# HMC5983_Breakout.net
KiCad netlist of a schematic drawn in EAGLE
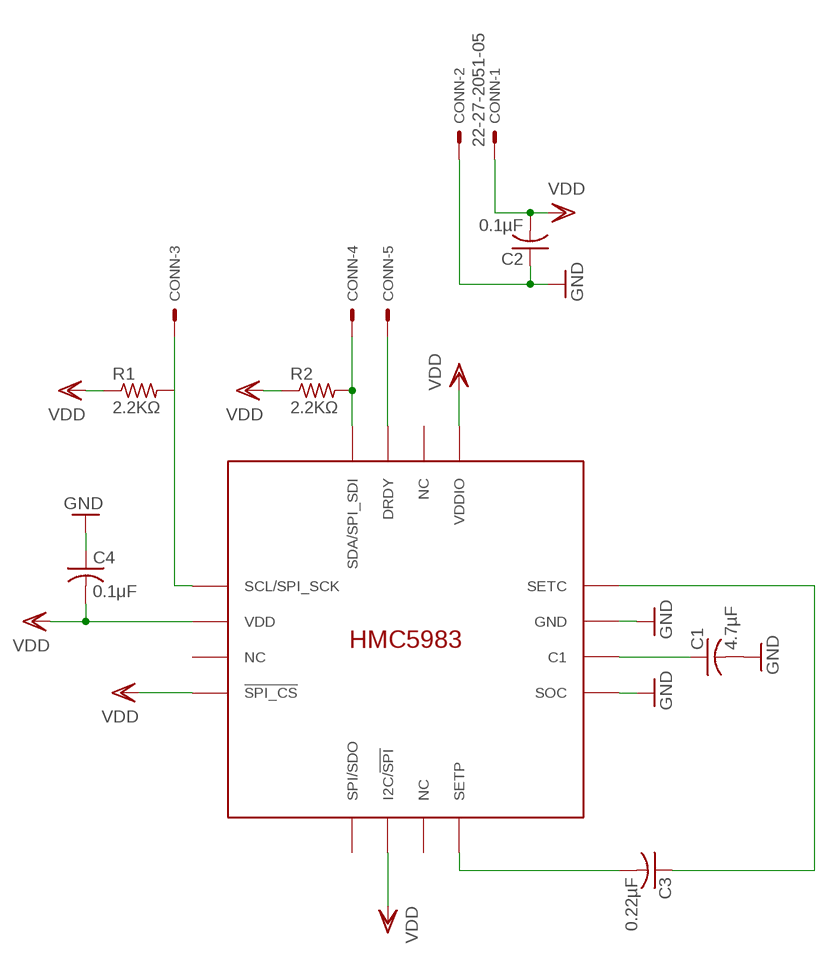
[diagram p0: schematic, sheet 1]

(export (version "E")
  (design (tool "Eeschema 10.0.6"))
  (components
    (comp (ref "C1")
      (value "4.7µF")
      (footprint "eagle-import:C0805")
      (libsource (lib "eagle-import") (part "C-USC0805"))
    )
    (comp (ref "C2")
      (value "0.1µF")
      (footprint "eagle-import:C0805")
      (libsource (lib "eagle-import") (part "C-USC0805"))
    )
    (comp (ref "C3")
      (value "0.22µF")
      (footprint "eagle-import:C0805")
      (libsource (lib "eagle-import") (part "C-USC0805"))
    )
    (comp (ref "C4")
      (value "0.1μF")
      (footprint "eagle-import:C0805")
      (libsource (lib "eagle-import") (part "C-USC0805"))
    )
    (comp (ref "CONN")
      (value "22-27-2051-05")
      (footprint "eagle-import:6410-05")
      (libsource (lib "eagle-import") (part "22-?-0527-2051"))
    )
    (comp (ref "R1")
      (value "2.2KΩ")
      (footprint "eagle-import:R0805")
      (libsource (lib "eagle-import") (part "R-US_R0805"))
    )
    (comp (ref "R2")
      (value "2.2KΩ")
      (footprint "eagle-import:R0805")
      (libsource (lib "eagle-import") (part "R-US_R0805"))
    )
    (comp (ref "U$1")
      (value "HMC5983")
      (footprint "eagle-import:HMC5983")
      (libsource (lib "eagle-import") (part "HMC5983"))
    )
  )
  (nets
    (net (code "1") (name "GND") (class "Default")
      (node (ref "C1") (pin "2") (pinfunction "2_2") (pintype "passive"))
      (node (ref "C2") (pin "1") (pinfunction "1_1") (pintype "passive"))
      (node (ref "C4") (pin "1") (pinfunction "1_1") (pintype "passive"))
      (node (ref "CONN") (pin "2") (pinfunction "S_2") (pintype "passive"))
      (node (ref "U$1") (pin "GND") (pinfunction "GND_GND") (pintype "bidirectional"))
      (node (ref "U$1") (pin "SOC") (pinfunction "SOC_SOC") (pintype "bidirectional"))
    )
    (net (code "2") (name "Net-(C1-Pad1)") (class "Default")
      (node (ref "C1") (pin "1") (pinfunction "1_1") (pintype "passive"))
      (node (ref "U$1") (pin "C1") (pinfunction "C1_C1") (pintype "bidirectional"))
    )
    (net (code "3") (name "Net-(C3-Pad1)") (class "Default")
      (node (ref "C3") (pin "1") (pinfunction "1_1") (pintype "passive"))
      (node (ref "U$1") (pin "SETC") (pinfunction "SETC_SETC") (pintype "bidirectional"))
    )
    (net (code "4") (name "Net-(C3-Pad2)") (class "Default")
      (node (ref "C3") (pin "2") (pinfunction "2_2") (pintype "passive"))
      (node (ref "U$1") (pin "SETP") (pinfunction "SETP_SETP") (pintype "bidirectional"))
    )
    (net (code "5") (name "Net-(CONNC-S)") (class "Default")
      (node (ref "CONN") (pin "3") (pinfunction "S_3") (pintype "passive"))
      (node (ref "R1") (pin "2") (pinfunction "2_2") (pintype "passive"))
      (node (ref "U$1") (pin "SCL/SPI_SCK") (pinfunction "SCL/SPI_SCK_SCL/SPI_SCK") (pintype "bidirectional"))
    )
    (net (code "6") (name "Net-(CONND-S)") (class "Default")
      (node (ref "CONN") (pin "4") (pinfunction "S_4") (pintype "passive"))
      (node (ref "R2") (pin "2") (pinfunction "2_2") (pintype "passive"))
      (node (ref "U$1") (pin "SDA/SPI_SDI") (pinfunction "SDA/SPI_SDI_SDA/SPI_SDI") (pintype "bidirectional"))
    )
    (net (code "7") (name "Net-(CONNE-S)") (class "Default")
      (node (ref "CONN") (pin "5") (pinfunction "S_5") (pintype "passive"))
      (node (ref "U$1") (pin "DRDY") (pinfunction "DRDY_DRDY") (pintype "bidirectional"))
    )
    (net (code "8") (name "VDD") (class "Default")
      (node (ref "C2") (pin "2") (pinfunction "2_2") (pintype "passive"))
      (node (ref "C4") (pin "2") (pinfunction "2_2") (pintype "passive"))
      (node (ref "CONN") (pin "1") (pinfunction "S_1") (pintype "passive"))
      (node (ref "R1") (pin "1") (pinfunction "1_1") (pintype "passive"))
      (node (ref "R2") (pin "1") (pinfunction "1_1") (pintype "passive"))
      (node (ref "U$1") (pin "!SPI_CS") (pinfunction "~{SPI_CS}_!SPI_CS") (pintype "bidirectional"))
      (node (ref "U$1") (pin "I2C/!SPI") (pinfunction "I2C/~{SPI}_I2C/!SPI") (pintype "bidirectional"))
      (node (ref "U$1") (pin "VDD") (pinfunction "VDD_VDD") (pintype "bidirectional"))
      (node (ref "U$1") (pin "VDDIO") (pinfunction "VDDIO_VDDIO") (pintype "bidirectional"))
    )
    (net (code "9") (name "unconnected-(U$1-NC-PadNC@1)") (class "Default")
      (node (ref "U$1") (pin "NC@1") (pinfunction "NC_NC@1") (pintype "bidirectional"))
    )
    (net (code "10") (name "unconnected-(U$1-NC-PadNC@2)") (class "Default")
      (node (ref "U$1") (pin "NC@2") (pinfunction "NC_NC@2") (pintype "bidirectional"))
    )
    (net (code "11") (name "unconnected-(U$1-NC-PadNC@3)") (class "Default")
      (node (ref "U$1") (pin "NC@3") (pinfunction "NC_NC@3") (pintype "bidirectional"))
    )
    (net (code "12") (name "unconnected-(U$1-SPI{slash}SDO-PadSPI_SDO)") (class "Default")
      (node (ref "U$1") (pin "SPI_SDO") (pinfunction "SPI/SDO_SPI_SDO") (pintype "bidirectional"))
    )
  )
)
